# INA169_Breakout.net
KiCad netlist of a schematic drawn in EAGLE
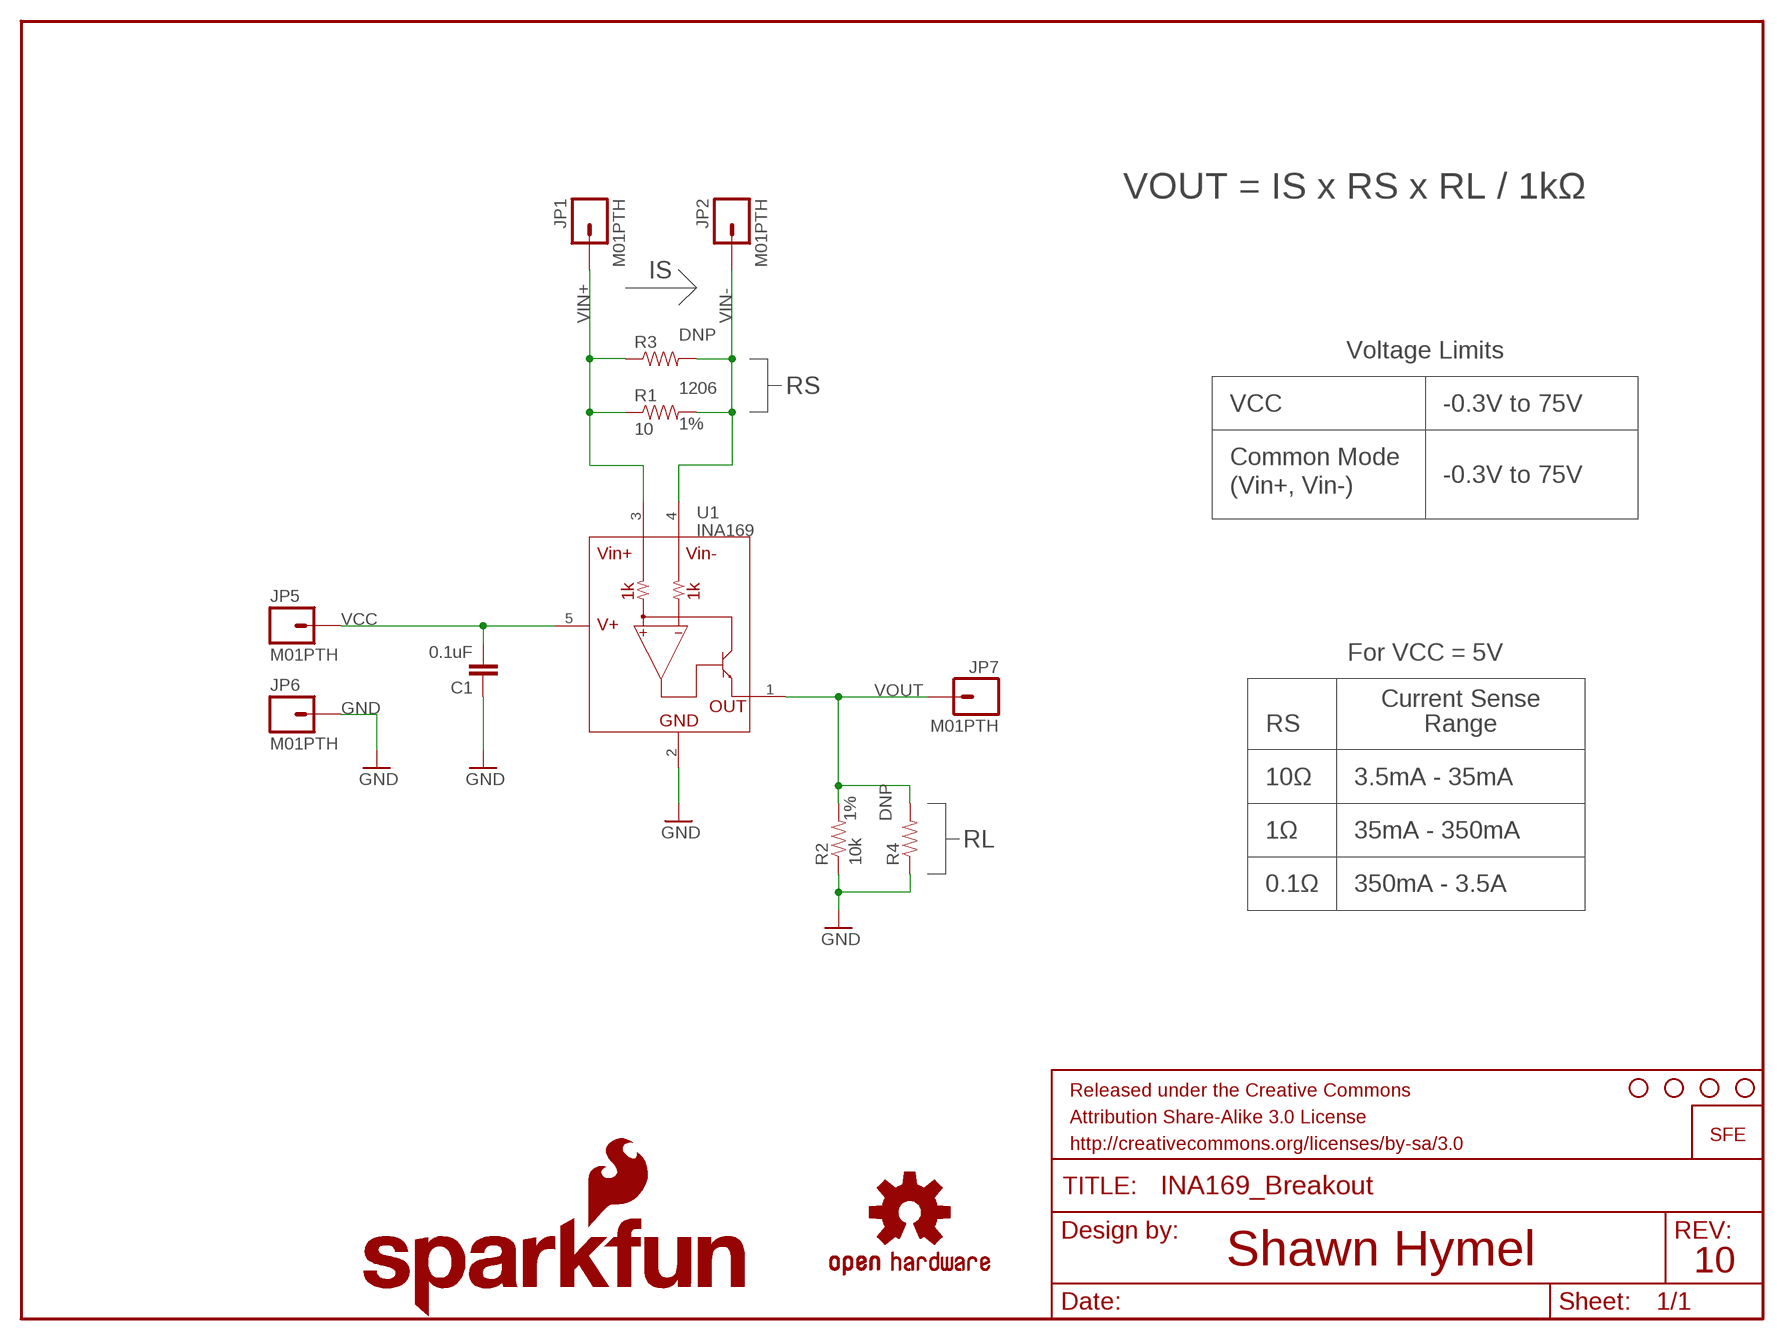
[diagram p0: schematic, sheet 1]

(export (version "E")
  (design (tool "Eeschema 10.0.6"))
  (components
    (comp (ref "C1")
      (value "0.1uF")
      (footprint "eagle-import:0603-CAP")
      (libsource (lib "eagle-import") (part "CAP0603-CAP"))
    )
    (comp (ref "FRAME1")
      (value "FRAME-LETTER")
      (footprint "eagle-import:CREATIVE_COMMONS")
      (libsource (lib "eagle-import") (part "FRAME-LETTER"))
    )
    (comp (ref "JP1")
      (value "M01PTH")
      (footprint "eagle-import:1X01")
      (libsource (lib "eagle-import") (part "M01PTH"))
    )
    (comp (ref "JP2")
      (value "M01PTH")
      (footprint "eagle-import:1X01")
      (libsource (lib "eagle-import") (part "M01PTH"))
    )
    (comp (ref "JP5")
      (value "M01PTH")
      (footprint "eagle-import:1X01")
      (libsource (lib "eagle-import") (part "M01PTH"))
    )
    (comp (ref "JP6")
      (value "M01PTH")
      (footprint "eagle-import:1X01")
      (libsource (lib "eagle-import") (part "M01PTH"))
    )
    (comp (ref "JP7")
      (value "M01PTH")
      (footprint "eagle-import:1X01")
      (libsource (lib "eagle-import") (part "M01PTH"))
    )
    (comp (ref "LOGO1")
      (value "SFE_LOGO_NAME_FLAME.1_INCH")
      (footprint "eagle-import:SFE_LOGO_NAME_FLAME_.1")
      (libsource (lib "eagle-import") (part "SFE_LOGO_NAME_FLAME.1_INCH"))
    )
    (comp (ref "LOGO2")
      (value "OSHW-LOGOS")
      (footprint "eagle-import:OSHW-LOGO-S")
      (libsource (lib "eagle-import") (part "OSHW-LOGOS"))
    )
    (comp (ref "LOGO3")
      (value "LOGO-SFESK")
      (footprint "eagle-import:SFE-LOGO-FLAME")
      (libsource (lib "eagle-import") (part "LOGO-SFESK"))
    )
    (comp (ref "R1")
      (value "10")
      (footprint "eagle-import:1206")
      (fields (field (name "SIZE") "1206") (field (name "TOL") "1%"))
      (libsource (lib "eagle-import") (part "RESISTOR1206"))
    )
    (comp (ref "R2")
      (value "10k")
      (footprint "eagle-import:0603-RES")
      (fields (field (name "TOL") "1%"))
      (libsource (lib "eagle-import") (part "RESISTOR0603"))
    )
    (comp (ref "R3")
      (value "RESISTORPTH-2W")
      (footprint "eagle-import:AXIAL-0.8")
      (fields (field (name "PLACE") "DNP"))
      (libsource (lib "eagle-import") (part "RESISTORPTH-2W"))
    )
    (comp (ref "R4")
      (value "RESISTORPTH-1/4W")
      (footprint "eagle-import:AXIAL-0.4")
      (fields (field (name "PLACE") "DNP"))
      (libsource (lib "eagle-import") (part "RESISTORPTH-1/4W"))
    )
    (comp (ref "STANDOFF1")
      (value "STAND-OFF")
      (footprint "eagle-import:STAND-OFF")
      (libsource (lib "eagle-import") (part "STAND-OFF"))
    )
    (comp (ref "STANDOFF2")
      (value "STAND-OFF")
      (footprint "eagle-import:STAND-OFF")
      (libsource (lib "eagle-import") (part "STAND-OFF"))
    )
    (comp (ref "STANDOFF3")
      (value "STAND-OFF")
      (footprint "eagle-import:STAND-OFF")
      (libsource (lib "eagle-import") (part "STAND-OFF"))
    )
    (comp (ref "STANDOFF4")
      (value "STAND-OFF")
      (footprint "eagle-import:STAND-OFF")
      (libsource (lib "eagle-import") (part "STAND-OFF"))
    )
    (comp (ref "U1")
      (value "INA169")
      (footprint "eagle-import:SOT23-5")
      (libsource (lib "eagle-import") (part "INA169"))
    )
  )
  (nets
    (net (code "1") (name "/VCC") (class "Default")
      (node (ref "C1") (pin "2") (pinfunction "2_2") (pintype "passive"))
      (node (ref "JP5") (pin "1") (pinfunction "1_1") (pintype "passive"))
      (node (ref "U1") (pin "5") (pinfunction "V+_5") (pintype "bidirectional"))
    )
    (net (code "2") (name "/VIN+") (class "Default")
      (node (ref "JP1") (pin "1") (pinfunction "1_1") (pintype "passive"))
      (node (ref "R1") (pin "1") (pinfunction "1_1") (pintype "passive"))
      (node (ref "R3") (pin "P$1") (pinfunction "1_P$1") (pintype "passive"))
      (node (ref "U1") (pin "3") (pinfunction "VIN+_3") (pintype "bidirectional"))
    )
    (net (code "3") (name "/VIN-") (class "Default")
      (node (ref "JP2") (pin "1") (pinfunction "1_1") (pintype "passive"))
      (node (ref "R1") (pin "2") (pinfunction "2_2") (pintype "passive"))
      (node (ref "R3") (pin "P$2") (pinfunction "2_P$2") (pintype "passive"))
      (node (ref "U1") (pin "4") (pinfunction "VIN-_4") (pintype "bidirectional"))
    )
    (net (code "4") (name "/VOUT") (class "Default")
      (node (ref "JP7") (pin "1") (pinfunction "1_1") (pintype "passive"))
      (node (ref "R2") (pin "2") (pinfunction "2_2") (pintype "passive"))
      (node (ref "R4") (pin "P$2") (pinfunction "2_P$2") (pintype "passive"))
      (node (ref "U1") (pin "1") (pinfunction "OUT_1") (pintype "bidirectional"))
    )
    (net (code "5") (name "GND") (class "Default")
      (node (ref "C1") (pin "1") (pinfunction "1_1") (pintype "passive"))
      (node (ref "JP6") (pin "1") (pinfunction "1_1") (pintype "passive"))
      (node (ref "R2") (pin "1") (pinfunction "1_1") (pintype "passive"))
      (node (ref "R4") (pin "P$1") (pinfunction "1_P$1") (pintype "passive"))
      (node (ref "U1") (pin "2") (pinfunction "GND_2") (pintype "bidirectional"))
    )
  )
)
